# PWM2CV_AtMega_2020-12-24_12-28-22.net
KiCad netlist of a schematic drawn in EasyEDA
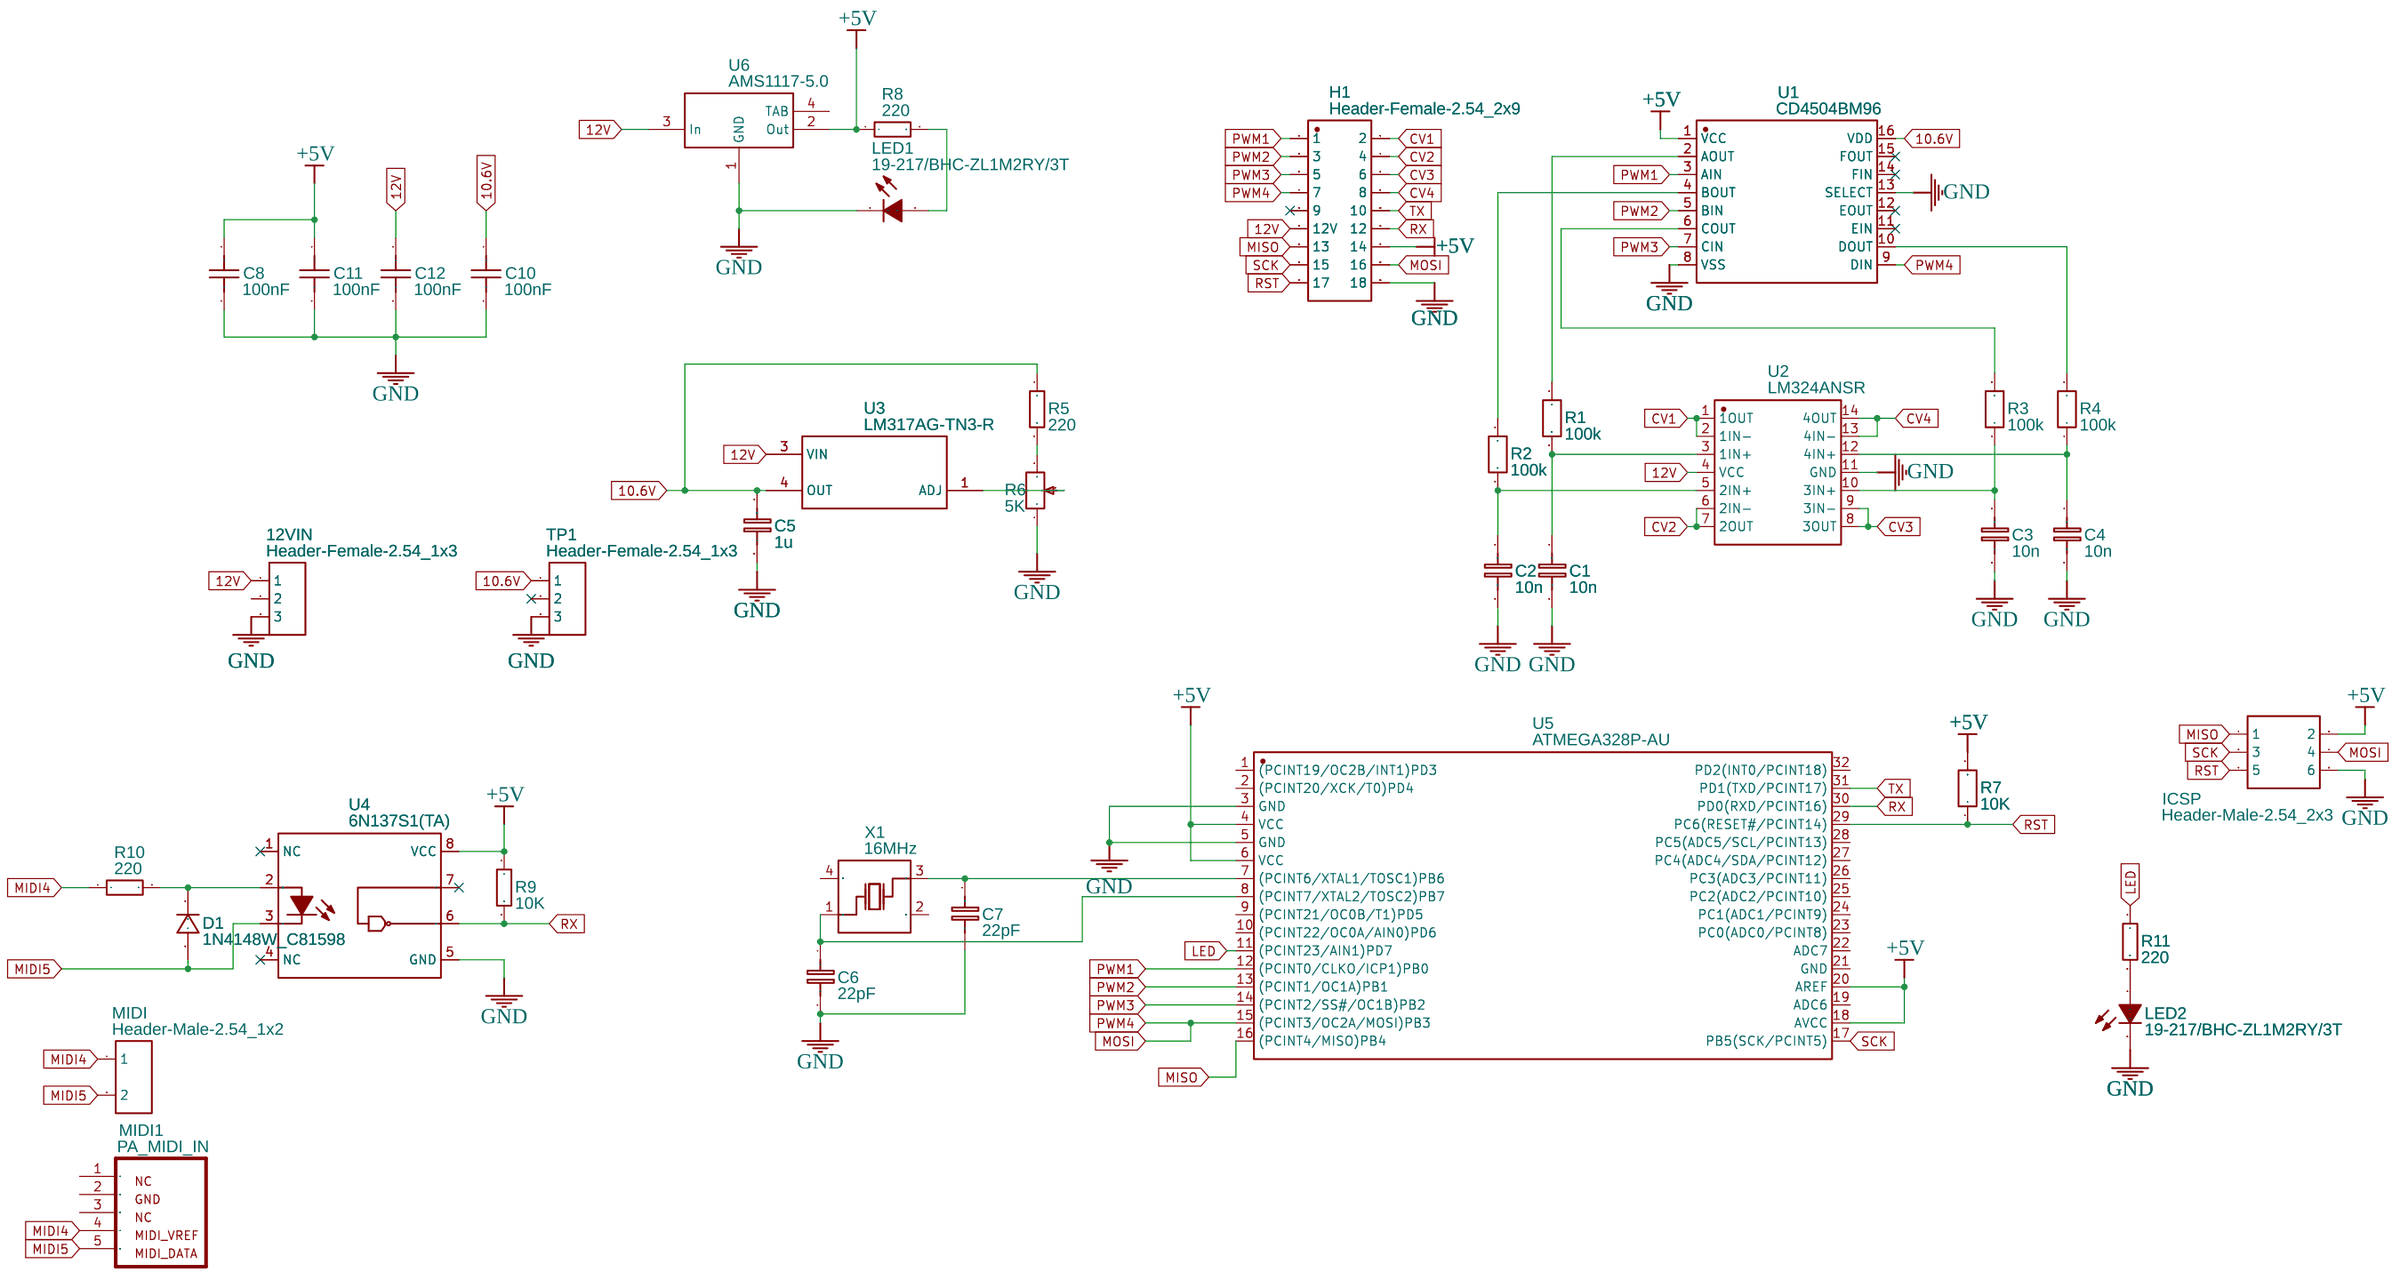
[diagram p0: schematic sheet]

(export (version "E")
  (design (tool "Eeschema 10.0.6"))
  (components
    (comp (ref "12VIN")
      (value "Header-Female-2.54_1x3")
      (fields (field (name "BOM_Supplier Part") "C146243"))
      (libsource (lib "") (part "Header-Female-2.54_1x3"))
    )
    (comp (ref "C1")
      (value "10n")
      (fields
        (field (name "BOM_Manufacturer Part") "0603B103K500NT")
        (field (name "BOM_Supplier Part") "C57112")
      )
      (libsource (lib "") (part "C_0603_EU"))
    )
    (comp (ref "C2")
      (value "10n")
      (fields
        (field (name "BOM_Manufacturer Part") "0603B103K500NT")
        (field (name "BOM_Supplier Part") "C57112")
      )
      (libsource (lib "") (part "C_0603_EU"))
    )
    (comp (ref "C3")
      (value "10n")
      (fields
        (field (name "BOM_Manufacturer Part") "0603B103K500NT")
        (field (name "BOM_Supplier Part") "C57112")
      )
      (libsource (lib "") (part "C_0603_EU_1"))
    )
    (comp (ref "C4")
      (value "10n")
      (fields
        (field (name "BOM_Manufacturer Part") "0603B103K500NT")
        (field (name "BOM_Supplier Part") "C57112")
      )
      (libsource (lib "") (part "C_0603_EU_1"))
    )
    (comp (ref "C5")
      (value "1u")
      (fields
        (field (name "BOM_Manufacturer Part") "CL10A105KB8NNNC")
        (field (name "BOM_Supplier Part") "C15849")
      )
      (libsource (lib "") (part "C_0603_EU_1"))
    )
    (comp (ref "C6")
      (value "22pF")
      (fields
        (field (name "BOM_Manufacturer Part") "CL10C220JB8NNNC")
        (field (name "BOM_Supplier Part") "C1653")
      )
      (libsource (lib "") (part "C_0603_EU_2"))
    )
    (comp (ref "C7")
      (value "22pF")
      (fields
        (field (name "BOM_Manufacturer Part") "CL10C220JB8NNNC")
        (field (name "BOM_Supplier Part") "C1653")
      )
      (libsource (lib "") (part "C_0603_EU_2"))
    )
    (comp (ref "C8")
      (value "100nF")
      (fields
        (field (name "BOM_Manufacturer Part") "CC0603KRX7R9BB104")
        (field (name "BOM_Supplier Part") "C14663")
      )
      (libsource (lib "") (part "CC0603KRX7R9BB104"))
    )
    (comp (ref "C10")
      (value "100nF")
      (fields
        (field (name "BOM_Manufacturer Part") "CC0603KRX7R9BB104")
        (field (name "BOM_Supplier Part") "C14663")
      )
      (libsource (lib "") (part "CC0603KRX7R9BB104"))
    )
    (comp (ref "C11")
      (value "100nF")
      (fields
        (field (name "BOM_Manufacturer Part") "CC0603KRX7R9BB104")
        (field (name "BOM_Supplier Part") "C14663")
      )
      (libsource (lib "") (part "CC0603KRX7R9BB104"))
    )
    (comp (ref "C12")
      (value "100nF")
      (fields
        (field (name "BOM_Manufacturer Part") "CC0603KRX7R9BB104")
        (field (name "BOM_Supplier Part") "C14663")
      )
      (libsource (lib "") (part "CC0603KRX7R9BB104"))
    )
    (comp (ref "D1")
      (value "1N4148W_C81598")
      (fields (field (name "BOM_Manufacturer Part") "1N4148W") (field (name "BOM_Supplier Part") "C81598"))
      (libsource (lib "") (part "1N4148W_C81598"))
    )
    (comp (ref "H1")
      (value "Header-Female-2.54_2x9")
      (fields (field (name "BOM_Supplier Part") "C71956"))
      (libsource (lib "") (part "Header-Female-2.54_2x9"))
    )
    (comp (ref "ICSP")
      (value "Header-Male-2.54_2x3")
      (fields (field (name "BOM_Supplier Part") "C65114"))
      (libsource (lib "") (part "Header-Male-2.54_2x3"))
    )
    (comp (ref "LED1")
      (value "19-217/BHC-ZL1M2RY/3T")
      (fields (field (name "BOM_Supplier Part") "C72041"))
      (libsource (lib "") (part "19-217/BHC-ZL1M2RY/3T"))
    )
    (comp (ref "LED2")
      (value "19-217/BHC-ZL1M2RY/3T")
      (fields (field (name "BOM_Supplier Part") "C72041"))
      (libsource (lib "") (part "19-217/BHC-ZL1M2RY/3T_1"))
    )
    (comp (ref "MIDI")
      (value "Header-Male-2.54_1x2")
      (fields (field (name "BOM_Manufacturer Part") "826629-2") (field (name "BOM_Supplier Part") "C86471"))
      (libsource (lib "") (part "Header-Male-2.54_1x2"))
    )
    (comp (ref "MIDI1") (value "PA_MIDI_IN") (libsource (lib "") (part "PA_MIDI_OUT")))
    (comp (ref "R1")
      (value "100k")
      (fields
        (field (name "BOM_Manufacturer Part") "0603WAF1003T5E")
        (field (name "BOM_Supplier Part") "C25803")
      )
      (libsource (lib "") (part "R_0603_EU_1"))
    )
    (comp (ref "R2")
      (value "100k")
      (fields
        (field (name "BOM_Manufacturer Part") "0603WAF1003T5E")
        (field (name "BOM_Supplier Part") "C25803")
      )
      (libsource (lib "") (part "R_0603_EU_1"))
    )
    (comp (ref "R3")
      (value "100k")
      (fields
        (field (name "BOM_Manufacturer Part") "0603WAF1003T5E")
        (field (name "BOM_Supplier Part") "C25803")
      )
      (libsource (lib "") (part "R_0603_EU"))
    )
    (comp (ref "R4")
      (value "100k")
      (fields
        (field (name "BOM_Manufacturer Part") "0603WAF1003T5E")
        (field (name "BOM_Supplier Part") "C25803")
      )
      (libsource (lib "") (part "R_0603_EU"))
    )
    (comp (ref "R5")
      (value "220")
      (fields
        (field (name "BOM_Manufacturer Part") "0603WAF2200T5E")
        (field (name "BOM_Supplier Part") "C22962")
      )
      (libsource (lib "") (part "0603WAF2200T5E"))
    )
    (comp (ref "R6")
      (value "5K")
      (fields
        (field (name "BOM_Manufacturer Part") "3314J-1-502E")
        (field (name "BOM_Supplier Part") "C58391")
      )
      (libsource (lib "") (part "3314J-1-502E"))
    )
    (comp (ref "R7")
      (value "10K")
      (fields
        (field (name "BOM_Manufacturer Part") "0603WAF1003T5E")
        (field (name "BOM_Supplier Part") "C25803")
      )
      (libsource (lib "") (part "R_0603_EU"))
    )
    (comp (ref "R8")
      (value "220")
      (fields
        (field (name "BOM_Manufacturer Part") "0603WAF2200T5E")
        (field (name "BOM_Supplier Part") "C22962")
      )
      (libsource (lib "") (part "0603WAF2200T5E_1"))
    )
    (comp (ref "R9")
      (value "10K")
      (fields
        (field (name "BOM_Manufacturer Part") "0603WAF1002T5E")
        (field (name "BOM_Supplier Part") "C25804")
      )
      (libsource (lib "") (part "0603WAF1002T5E"))
    )
    (comp (ref "R10")
      (value "220")
      (fields
        (field (name "BOM_Manufacturer Part") "0603WAF2200T5E")
        (field (name "BOM_Supplier Part") "C22962")
      )
      (libsource (lib "") (part "0603WAF2200T5E_1"))
    )
    (comp (ref "R11")
      (value "220")
      (fields
        (field (name "BOM_Manufacturer Part") "0603WAF2200T5E")
        (field (name "BOM_Supplier Part") "C22962")
      )
      (libsource (lib "") (part "0603WAF2200T5E"))
    )
    (comp (ref "TP1")
      (value "Header-Female-2.54_1x3")
      (fields (field (name "BOM_Supplier Part") "C146243"))
      (libsource (lib "") (part "Header-Female-2.54_1x3_1"))
    )
    (comp (ref "U1")
      (value "CD4504BM96")
      (fields (field (name "BOM_Supplier Part") "C151885"))
      (libsource (lib "") (part "CD4504BM96"))
    )
    (comp (ref "U2")
      (value "LM324ANSR")
      (fields (field (name "BOM_Supplier Part") "C111853"))
      (libsource (lib "") (part "LM324ANSR"))
    )
    (comp (ref "U3")
      (value "LM317AG-TN3-R")
      (fields (field (name "BOM_Supplier Part") "C75510"))
      (libsource (lib "") (part "LM317AG-TN3-R"))
    )
    (comp (ref "U4")
      (value "6N137S1(TA)")
      (fields (field (name "BOM_Supplier Part") "C110020"))
      (libsource (lib "") (part "6N137S1(TA)"))
    )
    (comp (ref "U5")
      (value "ATMEGA328P-AU")
      (fields (field (name "BOM_Supplier Part") "C14877"))
      (libsource (lib "") (part "ATMEGA328P-AU"))
    )
    (comp (ref "U6")
      (value "AMS1117-5.0")
      (fields (field (name "BOM_Supplier Part") "C6187"))
      (libsource (lib "") (part "AMS1117-5.0"))
    )
    (comp (ref "X1")
      (value "16MHz")
      (fields
        (field (name "BOM_Manufacturer Part") "X322516MLB4SI")
        (field (name "BOM_Supplier Part") "C13738")
      )
      (libsource (lib "") (part "X322516MLB4SI"))
    )
  )
  (nets
    (net (code "1") (name "+5V") (class "Default")
      (node (ref "C11") (pin "1") (pinfunction "1_1") (pintype "unspecified"))
      (node (ref "C8") (pin "1") (pinfunction "1_1") (pintype "unspecified"))
      (node (ref "H1") (pin "14") (pinfunction "14_14") (pintype "unspecified"))
      (node (ref "ICSP") (pin "2") (pinfunction "2_2") (pintype "input"))
      (node (ref "R7") (pin "2") (pinfunction "2_2") (pintype "unspecified"))
      (node (ref "R8") (pin "1") (pinfunction "1_1") (pintype "input"))
      (node (ref "R9") (pin "1") (pinfunction "1_1") (pintype "input"))
      (node (ref "U1") (pin "1") (pinfunction "VCC_1") (pintype "unspecified"))
      (node (ref "U4") (pin "8") (pinfunction "VCC_8") (pintype "unspecified"))
      (node (ref "U5") (pin "18") (pinfunction "AVCC_18") (pintype "unspecified"))
      (node (ref "U5") (pin "20") (pinfunction "AREF_20") (pintype "unspecified"))
      (node (ref "U5") (pin "4") (pinfunction "VCC_4") (pintype "unspecified"))
      (node (ref "U5") (pin "6") (pinfunction "VCC_6") (pintype "unspecified"))
      (node (ref "U6") (pin "2") (pinfunction "Out_2") (pintype "unspecified"))
    )
    (net (code "2") (name "10.6V") (class "Default")
      (node (ref "C10") (pin "1") (pinfunction "1_1") (pintype "unspecified"))
      (node (ref "C5") (pin "1") (pinfunction "1_1") (pintype "unspecified"))
      (node (ref "R5") (pin "1") (pinfunction "1_1") (pintype "input"))
      (node (ref "TP1") (pin "1") (pinfunction "1_1") (pintype "input"))
      (node (ref "U1") (pin "16") (pinfunction "VDD_16") (pintype "unspecified"))
      (node (ref "U3") (pin "4") (pinfunction "OUT_4") (pintype "unspecified"))
    )
    (net (code "3") (name "12V") (class "Default")
      (node (ref "12VIN") (pin "1") (pinfunction "1_1") (pintype "input"))
      (node (ref "C12") (pin "1") (pinfunction "1_1") (pintype "unspecified"))
      (node (ref "H1") (pin "11") (pinfunction "12V_11") (pintype "unspecified"))
      (node (ref "U2") (pin "4") (pinfunction "VCC_4") (pintype "unspecified"))
      (node (ref "U3") (pin "3") (pinfunction "VIN_3") (pintype "unspecified"))
      (node (ref "U6") (pin "3") (pinfunction "In_3") (pintype "unspecified"))
    )
    (net (code "4") (name "CV1") (class "Default")
      (node (ref "H1") (pin "2") (pinfunction "2_2") (pintype "unspecified"))
      (node (ref "U2") (pin "1") (pinfunction "1OUT_1") (pintype "unspecified"))
      (node (ref "U2") (pin "2") (pinfunction "1IN-_2") (pintype "unspecified"))
    )
    (net (code "5") (name "CV2") (class "Default")
      (node (ref "H1") (pin "4") (pinfunction "4_4") (pintype "unspecified"))
      (node (ref "U2") (pin "6") (pinfunction "2IN-_6") (pintype "unspecified"))
      (node (ref "U2") (pin "7") (pinfunction "2OUT_7") (pintype "unspecified"))
    )
    (net (code "6") (name "CV3") (class "Default")
      (node (ref "H1") (pin "6") (pinfunction "6_6") (pintype "unspecified"))
      (node (ref "U2") (pin "8") (pinfunction "3OUT_8") (pintype "unspecified"))
      (node (ref "U2") (pin "9") (pinfunction "3IN-_9") (pintype "unspecified"))
    )
    (net (code "7") (name "CV4") (class "Default")
      (node (ref "H1") (pin "8") (pinfunction "8_8") (pintype "unspecified"))
      (node (ref "U2") (pin "13") (pinfunction "4IN-_13") (pintype "unspecified"))
      (node (ref "U2") (pin "14") (pinfunction "4OUT_14") (pintype "unspecified"))
    )
    (net (code "8") (name "GND") (class "Default")
      (node (ref "12VIN") (pin "3") (pinfunction "3_3") (pintype "input"))
      (node (ref "C1") (pin "2") (pinfunction "2_2") (pintype "unspecified"))
      (node (ref "C10") (pin "2") (pinfunction "2_2") (pintype "unspecified"))
      (node (ref "C11") (pin "2") (pinfunction "2_2") (pintype "unspecified"))
      (node (ref "C12") (pin "2") (pinfunction "2_2") (pintype "unspecified"))
      (node (ref "C2") (pin "2") (pinfunction "2_2") (pintype "unspecified"))
      (node (ref "C3") (pin "2") (pinfunction "2_2") (pintype "unspecified"))
      (node (ref "C4") (pin "2") (pinfunction "2_2") (pintype "unspecified"))
      (node (ref "C5") (pin "2") (pinfunction "2_2") (pintype "unspecified"))
      (node (ref "C6") (pin "2") (pinfunction "2_2") (pintype "unspecified"))
      (node (ref "C7") (pin "2") (pinfunction "2_2") (pintype "unspecified"))
      (node (ref "C8") (pin "2") (pinfunction "2_2") (pintype "unspecified"))
      (node (ref "H1") (pin "18") (pinfunction "18_18") (pintype "unspecified"))
      (node (ref "ICSP") (pin "6") (pinfunction "6_6") (pintype "input"))
      (node (ref "LED1") (pin "2") (pinfunction "C_2") (pintype "input"))
      (node (ref "LED2") (pin "2") (pinfunction "C_2") (pintype "input"))
      (node (ref "R6") (pin "1") (pinfunction "1_1") (pintype "input"))
      (node (ref "TP1") (pin "3") (pinfunction "3_3") (pintype "input"))
      (node (ref "U1") (pin "13") (pinfunction "SELECT_13") (pintype "unspecified"))
      (node (ref "U1") (pin "8") (pinfunction "VSS_8") (pintype "unspecified"))
      (node (ref "U2") (pin "11") (pinfunction "GND_11") (pintype "unspecified"))
      (node (ref "U4") (pin "5") (pinfunction "GND_5") (pintype "unspecified"))
      (node (ref "U5") (pin "3") (pinfunction "GND_3") (pintype "unspecified"))
      (node (ref "U5") (pin "5") (pinfunction "GND_5") (pintype "unspecified"))
      (node (ref "U6") (pin "1") (pinfunction "GND_1") (pintype "unspecified"))
    )
    (net (code "9") (name "LED") (class "Default")
      (node (ref "R11") (pin "1") (pinfunction "1_1") (pintype "input"))
      (node (ref "U5") (pin "11") (pinfunction "(PCINT23/AIN1)PD7_11") (pintype "unspecified"))
    )
    (net (code "10") (name "MIDI4") (class "Default")
      (node (ref "MIDI") (pin "1") (pinfunction "1_1") (pintype "unspecified"))
      (node (ref "MIDI1") (pin "4") (pinfunction "4_4") (pintype "unspecified"))
      (node (ref "R10") (pin "1") (pinfunction "1_1") (pintype "input"))
    )
    (net (code "11") (name "MIDI5") (class "Default")
      (node (ref "D1") (pin "2") (pinfunction "A_2") (pintype "unspecified"))
      (node (ref "MIDI") (pin "2") (pinfunction "2_2") (pintype "unspecified"))
      (node (ref "MIDI1") (pin "5") (pinfunction "5_5") (pintype "unspecified"))
      (node (ref "U4") (pin "3") (pinfunction "CAT_3") (pintype "unspecified"))
    )
    (net (code "12") (name "MISO") (class "Default")
      (node (ref "H1") (pin "13") (pinfunction "13_13") (pintype "unspecified"))
      (node (ref "ICSP") (pin "1") (pinfunction "1_1") (pintype "input"))
      (node (ref "U5") (pin "16") (pinfunction "(PCINT4/MISO)PB4_16") (pintype "unspecified"))
    )
    (net (code "13") (name "MOSI") (class "Default")
      (node (ref "H1") (pin "16") (pinfunction "16_16") (pintype "unspecified"))
      (node (ref "H1") (pin "7") (pinfunction "7_7") (pintype "unspecified"))
      (node (ref "ICSP") (pin "4") (pinfunction "4_4") (pintype "input"))
      (node (ref "U1") (pin "9") (pinfunction "DIN_9") (pintype "unspecified"))
      (node (ref "U5") (pin "15") (pinfunction "(PCINT3/OC2A/MOSI)PB3_15") (pintype "unspecified"))
    )
    (net (code "14") (name "Net-(D1-K)") (class "Default")
      (node (ref "D1") (pin "1") (pinfunction "K_1") (pintype "unspecified"))
      (node (ref "R10") (pin "2") (pinfunction "2_2") (pintype "input"))
      (node (ref "U4") (pin "2") (pinfunction "AN_2") (pintype "unspecified"))
    )
    (net (code "15") (name "Net-(LED1-A)") (class "Default")
      (node (ref "LED1") (pin "1") (pinfunction "A_1") (pintype "input"))
      (node (ref "R8") (pin "2") (pinfunction "2_2") (pintype "input"))
    )
    (net (code "16") (name "Net-(LED2-A)") (class "Default")
      (node (ref "LED2") (pin "1") (pinfunction "A_1") (pintype "input"))
      (node (ref "R11") (pin "2") (pinfunction "2_2") (pintype "input"))
    )
    (net (code "17") (name "Net-(R5-Pad2)") (class "Default")
      (node (ref "R5") (pin "2") (pinfunction "2_2") (pintype "input"))
      (node (ref "R6") (pin "3") (pinfunction "3_3") (pintype "input"))
    )
    (net (code "18") (name "Net-(U1-AOUT)") (class "Default")
      (node (ref "R1") (pin "1") (pinfunction "1_1") (pintype "unspecified"))
      (node (ref "U1") (pin "2") (pinfunction "AOUT_2") (pintype "unspecified"))
    )
    (net (code "19") (name "Net-(U1-BOUT)") (class "Default")
      (node (ref "R2") (pin "1") (pinfunction "1_1") (pintype "unspecified"))
      (node (ref "U1") (pin "4") (pinfunction "BOUT_4") (pintype "unspecified"))
    )
    (net (code "20") (name "Net-(U1-COUT)") (class "Default")
      (node (ref "R3") (pin "2") (pinfunction "2_2") (pintype "unspecified"))
      (node (ref "U1") (pin "6") (pinfunction "COUT_6") (pintype "unspecified"))
    )
    (net (code "21") (name "Net-(U1-DOUT)") (class "Default")
      (node (ref "R4") (pin "2") (pinfunction "2_2") (pintype "unspecified"))
      (node (ref "U1") (pin "10") (pinfunction "DOUT_10") (pintype "unspecified"))
    )
    (net (code "22") (name "Net-(U2-1IN+)") (class "Default")
      (node (ref "C1") (pin "1") (pinfunction "1_1") (pintype "unspecified"))
      (node (ref "R1") (pin "2") (pinfunction "2_2") (pintype "unspecified"))
      (node (ref "U2") (pin "3") (pinfunction "1IN+_3") (pintype "unspecified"))
    )
    (net (code "23") (name "Net-(U2-2IN+)") (class "Default")
      (node (ref "C2") (pin "1") (pinfunction "1_1") (pintype "unspecified"))
      (node (ref "R2") (pin "2") (pinfunction "2_2") (pintype "unspecified"))
      (node (ref "U2") (pin "5") (pinfunction "2IN+_5") (pintype "unspecified"))
    )
    (net (code "24") (name "Net-(U2-3IN+)") (class "Default")
      (node (ref "C3") (pin "1") (pinfunction "1_1") (pintype "unspecified"))
      (node (ref "R3") (pin "1") (pinfunction "1_1") (pintype "unspecified"))
      (node (ref "U2") (pin "10") (pinfunction "3IN+_10") (pintype "unspecified"))
    )
    (net (code "25") (name "Net-(U2-4IN+)") (class "Default")
      (node (ref "C4") (pin "1") (pinfunction "1_1") (pintype "unspecified"))
      (node (ref "R4") (pin "1") (pinfunction "1_1") (pintype "unspecified"))
      (node (ref "U2") (pin "12") (pinfunction "4IN+_12") (pintype "unspecified"))
    )
    (net (code "26") (name "Net-(U3-ADJ)") (class "Default")
      (node (ref "R6") (pin "2") (pinfunction "2_2") (pintype "input"))
      (node (ref "U3") (pin "1") (pinfunction "ADJ_1") (pintype "unspecified"))
    )
    (net (code "27") (name "Net-(U5-(PCINT6{slash}XTAL1{slash}TOSC1)PB6)") (class "Default")
      (node (ref "C7") (pin "1") (pinfunction "1_1") (pintype "unspecified"))
      (node (ref "U5") (pin "7") (pinfunction "(PCINT6/XTAL1/TOSC1)PB6_7") (pintype "unspecified"))
      (node (ref "X1") (pin "3") (pinfunction "OSC2_3") (pintype "unspecified"))
    )
    (net (code "28") (name "Net-(U5-(PCINT7{slash}XTAL2{slash}TOSC2)PB7)") (class "Default")
      (node (ref "C6") (pin "1") (pinfunction "1_1") (pintype "unspecified"))
      (node (ref "U5") (pin "8") (pinfunction "(PCINT7/XTAL2/TOSC2)PB7_8") (pintype "unspecified"))
      (node (ref "X1") (pin "1") (pinfunction "OSC1_1") (pintype "unspecified"))
    )
    (net (code "29") (name "PWM1") (class "Default")
      (node (ref "H1") (pin "1") (pinfunction "1_1") (pintype "unspecified"))
      (node (ref "U1") (pin "3") (pinfunction "AIN_3") (pintype "unspecified"))
      (node (ref "U5") (pin "12") (pinfunction "(PCINT0/CLKO/ICP1)PB0_12") (pintype "unspecified"))
    )
    (net (code "30") (name "PWM2") (class "Default")
      (node (ref "H1") (pin "3") (pinfunction "3_3") (pintype "unspecified"))
      (node (ref "U1") (pin "5") (pinfunction "BIN_5") (pintype "unspecified"))
      (node (ref "U5") (pin "13") (pinfunction "(PCINT1/OC1A)PB1_13") (pintype "unspecified"))
    )
    (net (code "31") (name "PWM3") (class "Default")
      (node (ref "H1") (pin "5") (pinfunction "5_5") (pintype "unspecified"))
      (node (ref "U1") (pin "7") (pinfunction "CIN_7") (pintype "unspecified"))
      (node (ref "U5") (pin "14") (pinfunction "(PCINT2/SS#/OC1B)PB2_14") (pintype "unspecified"))
    )
    (net (code "32") (name "RST") (class "Default")
      (node (ref "H1") (pin "17") (pinfunction "17_17") (pintype "unspecified"))
      (node (ref "ICSP") (pin "5") (pinfunction "5_5") (pintype "input"))
      (node (ref "R7") (pin "1") (pinfunction "1_1") (pintype "unspecified"))
      (node (ref "U5") (pin "29") (pinfunction "PC6(RESET#/PCINT14)_29") (pintype "unspecified"))
    )
    (net (code "33") (name "RX") (class "Default")
      (node (ref "H1") (pin "12") (pinfunction "12_12") (pintype "unspecified"))
      (node (ref "R9") (pin "2") (pinfunction "2_2") (pintype "input"))
      (node (ref "U4") (pin "6") (pinfunction "VOUT_6") (pintype "unspecified"))
      (node (ref "U5") (pin "30") (pinfunction "PD0(RXD/PCINT16)_30") (pintype "unspecified"))
    )
    (net (code "34") (name "SCK") (class "Default")
      (node (ref "H1") (pin "15") (pinfunction "15_15") (pintype "unspecified"))
      (node (ref "ICSP") (pin "3") (pinfunction "3_3") (pintype "input"))
      (node (ref "U5") (pin "17") (pinfunction "PB5(SCK/PCINT5)_17") (pintype "unspecified"))
    )
    (net (code "35") (name "TX") (class "Default")
      (node (ref "H1") (pin "10") (pinfunction "10_10") (pintype "unspecified"))
      (node (ref "U5") (pin "31") (pinfunction "PD1(TXD/PCINT17)_31") (pintype "unspecified"))
    )
    (net (code "36") (name "unconnected-(12VIN-Pad2)") (class "Default")
      (node (ref "12VIN") (pin "2") (pinfunction "2_2") (pintype "input"))
    )
    (net (code "37") (name "unconnected-(H1-Pad9)") (class "Default")
      (node (ref "H1") (pin "9") (pinfunction "9_9") (pintype "unspecified+no_connect"))
    )
    (net (code "38") (name "unconnected-(MIDI1-Pad1)") (class "Default")
      (node (ref "MIDI1") (pin "1") (pinfunction "1_1") (pintype "unspecified"))
    )
    (net (code "39") (name "unconnected-(MIDI1-Pad2)") (class "Default")
      (node (ref "MIDI1") (pin "2") (pinfunction "2_2") (pintype "unspecified"))
    )
    (net (code "40") (name "unconnected-(MIDI1-Pad3)") (class "Default")
      (node (ref "MIDI1") (pin "3") (pinfunction "3_3") (pintype "unspecified"))
    )
    (net (code "41") (name "unconnected-(TP1-Pad2)") (class "Default")
      (node (ref "TP1") (pin "2") (pinfunction "2_2") (pintype "input+no_connect"))
    )
    (net (code "42") (name "unconnected-(U1-EIN-Pad11)") (class "Default")
      (node (ref "U1") (pin "11") (pinfunction "EIN_11") (pintype "unspecified+no_connect"))
    )
    (net (code "43") (name "unconnected-(U1-EOUT-Pad12)") (class "Default")
      (node (ref "U1") (pin "12") (pinfunction "EOUT_12") (pintype "unspecified+no_connect"))
    )
    (net (code "44") (name "unconnected-(U1-FIN-Pad14)") (class "Default")
      (node (ref "U1") (pin "14") (pinfunction "FIN_14") (pintype "unspecified+no_connect"))
    )
    (net (code "45") (name "unconnected-(U1-FOUT-Pad15)") (class "Default")
      (node (ref "U1") (pin "15") (pinfunction "FOUT_15") (pintype "unspecified+no_connect"))
    )
    (net (code "46") (name "unconnected-(U4-NC-Pad1)") (class "Default")
      (node (ref "U4") (pin "1") (pinfunction "NC_1") (pintype "unspecified+no_connect"))
    )
    (net (code "47") (name "unconnected-(U4-NC-Pad4)") (class "Default")
      (node (ref "U4") (pin "4") (pinfunction "NC_4") (pintype "unspecified+no_connect"))
    )
    (net (code "48") (name "unconnected-(U4-VE-Pad7)") (class "Default")
      (node (ref "U4") (pin "7") (pinfunction "VE_7") (pintype "unspecified+no_connect"))
    )
    (net (code "49") (name "unconnected-(U5-(PCINT19{slash}OC2B{slash}INT1)PD3-Pad1)") (class "Default")
      (node (ref "U5") (pin "1") (pinfunction "(PCINT19/OC2B/INT1)PD3_1") (pintype "unspecified"))
    )
    (net (code "50") (name "unconnected-(U5-(PCINT20{slash}XCK{slash}T0)PD4-Pad2)") (class "Default")
      (node (ref "U5") (pin "2") (pinfunction "(PCINT20/XCK/T0)PD4_2") (pintype "unspecified"))
    )
    (net (code "51") (name "unconnected-(U5-(PCINT21{slash}OC0B{slash}T1)PD5-Pad9)") (class "Default")
      (node (ref "U5") (pin "9") (pinfunction "(PCINT21/OC0B/T1)PD5_9") (pintype "unspecified"))
    )
    (net (code "52") (name "unconnected-(U5-(PCINT22{slash}OC0A{slash}AIN0)PD6-Pad10)") (class "Default")
      (node (ref "U5") (pin "10") (pinfunction "(PCINT22/OC0A/AIN0)PD6_10") (pintype "unspecified"))
    )
    (net (code "53") (name "unconnected-(U5-ADC6-Pad19)") (class "Default")
      (node (ref "U5") (pin "19") (pinfunction "ADC6_19") (pintype "unspecified"))
    )
    (net (code "54") (name "unconnected-(U5-ADC7-Pad22)") (class "Default")
      (node (ref "U5") (pin "22") (pinfunction "ADC7_22") (pintype "unspecified"))
    )
    (net (code "55") (name "unconnected-(U5-GND-Pad21)") (class "Default")
      (node (ref "U5") (pin "21") (pinfunction "GND_21") (pintype "unspecified"))
    )
    (net (code "56") (name "unconnected-(U5-PC0(ADC0{slash}PCINT8)-Pad23)") (class "Default")
      (node (ref "U5") (pin "23") (pinfunction "PC0(ADC0/PCINT8)_23") (pintype "unspecified"))
    )
    (net (code "57") (name "unconnected-(U5-PC1(ADC1{slash}PCINT9)-Pad24)") (class "Default")
      (node (ref "U5") (pin "24") (pinfunction "PC1(ADC1/PCINT9)_24") (pintype "unspecified"))
    )
    (net (code "58") (name "unconnected-(U5-PC2(ADC2{slash}PCINT10)-Pad25)") (class "Default")
      (node (ref "U5") (pin "25") (pinfunction "PC2(ADC2/PCINT10)_25") (pintype "unspecified"))
    )
    (net (code "59") (name "unconnected-(U5-PC3(ADC3{slash}PCINT11)-Pad26)") (class "Default")
      (node (ref "U5") (pin "26") (pinfunction "PC3(ADC3/PCINT11)_26") (pintype "unspecified"))
    )
    (net (code "60") (name "unconnected-(U5-PC4(ADC4{slash}SDA{slash}PCINT12)-Pad27)") (class "Default")
      (node (ref "U5") (pin "27") (pinfunction "PC4(ADC4/SDA/PCINT12)_27") (pintype "unspecified"))
    )
    (net (code "61") (name "unconnected-(U5-PC5(ADC5{slash}SCL{slash}PCINT13)-Pad28)") (class "Default")
      (node (ref "U5") (pin "28") (pinfunction "PC5(ADC5/SCL/PCINT13)_28") (pintype "unspecified"))
    )
    (net (code "62") (name "unconnected-(U5-PD2(INT0{slash}PCINT18)-Pad32)") (class "Default")
      (node (ref "U5") (pin "32") (pinfunction "PD2(INT0/PCINT18)_32") (pintype "unspecified"))
    )
    (net (code "63") (name "unconnected-(U6-TAB-Pad4)") (class "Default")
      (node (ref "U6") (pin "4") (pinfunction "TAB_4") (pintype "unspecified"))
    )
    (net (code "64") (name "unconnected-(X1-GND-Pad2)") (class "Default")
      (node (ref "X1") (pin "2") (pinfunction "GND_2") (pintype "unspecified"))
    )
    (net (code "65") (name "unconnected-(X1-GND-Pad4)") (class "Default")
      (node (ref "X1") (pin "4") (pinfunction "GND_4") (pintype "unspecified"))
    )
  )
)
